# TAG.net
KiCad netlist of a schematic drawn in Altium Designer
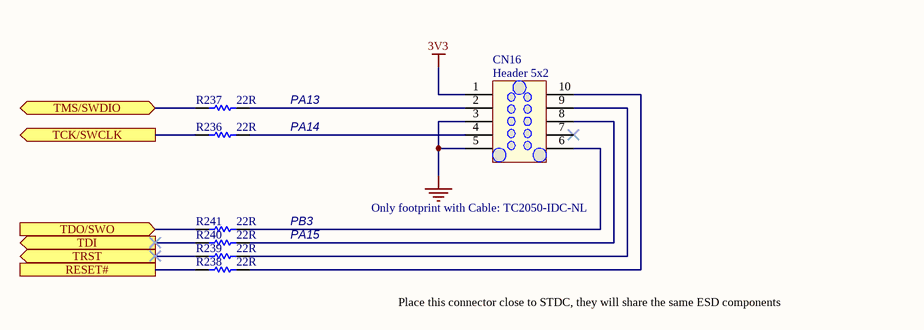
[diagram p0: TAG.SchDoc]

(export (version "E")
  (design (tool "Eeschema 10.0.6"))
  (components
    (comp (ref "CN16")
      (value "Header 5x2")
      (footprint "CON_TAG-C_TC2050-IDC-NL")
      (description "Tag_Connector Header, 10x2, No legs")
      (fields
        (field (name "INTERNAL_PART_NUMBER") "MCD-00031")
        (field (name "Comment") "Tag-10-C")
        (field (name "PROVIDED_BY") "Subcon")
      )
      (libsource (lib "MCD_PARTS_database") (part "Tag-10-C"))
    )
    (comp (ref "R236")
      (value "22R")
      (footprint "R0402")
      (description "Resistor,22R,0402,1%,1/16W")
      (fields
        (field (name "INTERNAL_PART_NUMBER") "MCD-00189")
        (field (name "MANUFACTURER_PART_NUMBER") "RC0402FR-0722RL")
        (field (name "PROVIDED_BY") "Subcon")
      )
      (libsource (lib "MCD_PARTS_database") (part "Resistor"))
    )
    (comp (ref "R237")
      (value "22R")
      (footprint "R0402")
      (description "Resistor,22R,0402,1%,1/16W")
      (fields
        (field (name "INTERNAL_PART_NUMBER") "MCD-00189")
        (field (name "MANUFACTURER_PART_NUMBER") "RC0402FR-0722RL")
        (field (name "PROVIDED_BY") "Subcon")
      )
      (libsource (lib "MCD_PARTS_database") (part "Resistor"))
    )
    (comp (ref "R238")
      (value "22R")
      (footprint "R0402")
      (description "Resistor,22R,0402,1%,1/16W")
      (fields
        (field (name "INTERNAL_PART_NUMBER") "MCD-00189")
        (field (name "MANUFACTURER_PART_NUMBER") "RC0402FR-0722RL")
        (field (name "PROVIDED_BY") "Subcon")
      )
      (libsource (lib "MCD_PARTS_database") (part "Resistor"))
    )
    (comp (ref "R239")
      (value "22R")
      (footprint "R0402")
      (description "Resistor,22R,0402,1%,1/16W")
      (fields
        (field (name "INTERNAL_PART_NUMBER") "MCD-00189")
        (field (name "MANUFACTURER_PART_NUMBER") "RC0402FR-0722RL")
        (field (name "PROVIDED_BY") "Subcon")
      )
      (libsource (lib "MCD_PARTS_database") (part "Resistor"))
    )
    (comp (ref "R240")
      (value "22R")
      (footprint "R0402")
      (description "Resistor,22R,0402,1%,1/16W")
      (fields
        (field (name "INTERNAL_PART_NUMBER") "MCD-00189")
        (field (name "MANUFACTURER_PART_NUMBER") "RC0402FR-0722RL")
        (field (name "PROVIDED_BY") "Subcon")
      )
      (libsource (lib "MCD_PARTS_database") (part "Resistor"))
    )
    (comp (ref "R241")
      (value "22R")
      (footprint "R0402")
      (description "Resistor,22R,0402,1%,1/16W")
      (fields
        (field (name "INTERNAL_PART_NUMBER") "MCD-00189")
        (field (name "MANUFACTURER_PART_NUMBER") "RC0402FR-0722RL")
        (field (name "PROVIDED_BY") "Subcon")
      )
      (libsource (lib "MCD_PARTS_database") (part "Resistor"))
    )
  )
  (nets
    (net (code "1") (name "/RESET#") (class "Default")
      (node (ref "R238") (pin "1") (pinfunction "1_1") (pintype "passive"))
    )
    (net (code "2") (name "/TCK{slash}SWCLK") (class "Default")
      (node (ref "R236") (pin "1") (pinfunction "1_1") (pintype "passive"))
    )
    (net (code "3") (name "/TDI") (class "Default")
      (node (ref "R240") (pin "1") (pinfunction "1_1") (pintype "passive+no_connect"))
    )
    (net (code "4") (name "/TDO{slash}SWO") (class "Default")
      (node (ref "R241") (pin "1") (pinfunction "1_1") (pintype "passive"))
    )
    (net (code "5") (name "/TMS{slash}SWDIO") (class "Default")
      (node (ref "R237") (pin "1") (pinfunction "1_1") (pintype "passive"))
    )
    (net (code "6") (name "/TRST") (class "Default")
      (node (ref "R239") (pin "1") (pinfunction "1_1") (pintype "passive+no_connect"))
    )
    (net (code "7") (name "3V3") (class "Default")
      (node (ref "CN16") (pin "1") (pinfunction "1_1") (pintype "passive"))
    )
    (net (code "8") (name "GND") (class "Default")
      (node (ref "CN16") (pin "3") (pinfunction "3_3") (pintype "passive"))
      (node (ref "CN16") (pin "5") (pinfunction "5_5") (pintype "passive"))
    )
    (net (code "9") (name "Net-(CN16-Pad2)") (class "Default")
      (node (ref "CN16") (pin "2") (pinfunction "2_2") (pintype "passive"))
      (node (ref "R237") (pin "2") (pinfunction "2_2") (pintype "passive"))
    )
    (net (code "10") (name "Net-(CN16-Pad4)") (class "Default")
      (node (ref "CN16") (pin "4") (pinfunction "4_4") (pintype "passive"))
      (node (ref "R236") (pin "2") (pinfunction "2_2") (pintype "passive"))
    )
    (net (code "11") (name "Net-(CN16-Pad6)") (class "Default")
      (node (ref "CN16") (pin "6") (pinfunction "6_6") (pintype "passive"))
      (node (ref "R241") (pin "2") (pinfunction "2_2") (pintype "passive"))
    )
    (net (code "12") (name "Net-(CN16-Pad8)") (class "Default")
      (node (ref "CN16") (pin "8") (pinfunction "8_8") (pintype "passive"))
      (node (ref "R240") (pin "2") (pinfunction "2_2") (pintype "passive"))
    )
    (net (code "13") (name "Net-(CN16-Pad9)") (class "Default")
      (node (ref "CN16") (pin "9") (pinfunction "9_9") (pintype "passive"))
      (node (ref "R239") (pin "2") (pinfunction "2_2") (pintype "passive"))
    )
    (net (code "14") (name "Net-(CN16-Pad10)") (class "Default")
      (node (ref "CN16") (pin "10") (pinfunction "10_10") (pintype "passive"))
      (node (ref "R238") (pin "2") (pinfunction "2_2") (pintype "passive"))
    )
    (net (code "15") (name "unconnected-(CN16-Pad7)") (class "Default")
      (node (ref "CN16") (pin "7") (pinfunction "7_7") (pintype "passive+no_connect"))
    )
  )
)
